# yuh.net
KiCad netlist of a schematic drawn in EAGLE
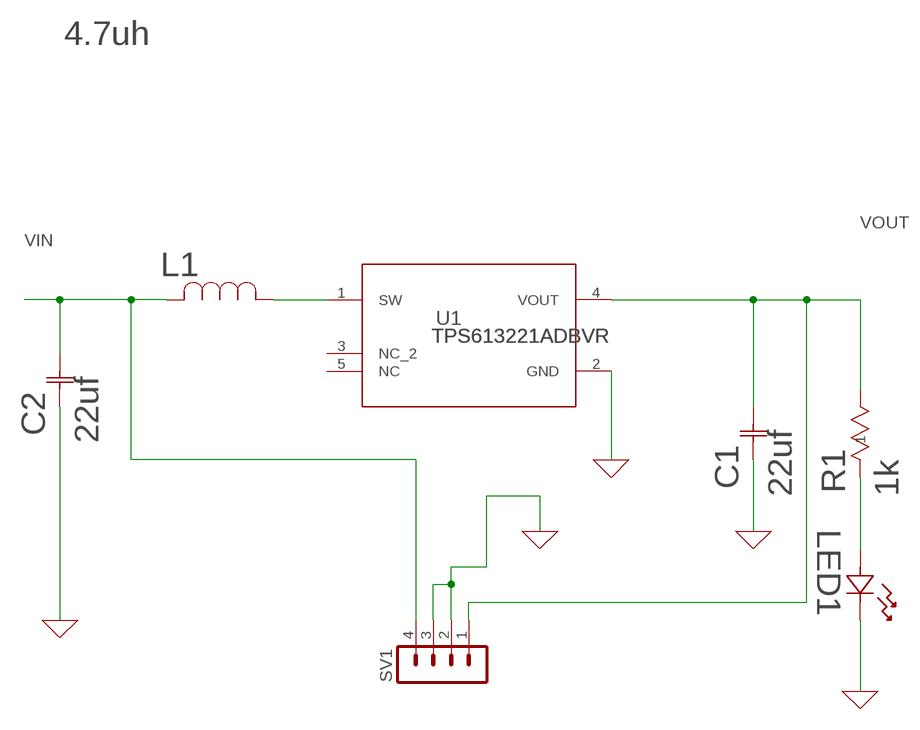
[diagram p0: schematic, sheet 1]

(export (version "E")
  (design (tool "Eeschema 10.0.6"))
  (components
    (comp (ref "C1")
      (value "22uf")
      (footprint "eagle-import:CAP_CL21_SAM")
      (fields
        (field (name "MANUFACTURER_PART_NUMBER") "CL21A226MQQNNNE")
        (field (name "COPYRIGHT") "Copyright (C) 2024 Ultra Librarian. All rights reserved.")
      )
      (libsource (lib "eagle-import") (part "CL21A226MQQNNNE"))
    )
    (comp (ref "C2")
      (value "22uf")
      (footprint "eagle-import:CAP_CL21_SAM")
      (fields
        (field (name "MANUFACTURER_PART_NUMBER") "CL21A226MQQNNNE")
        (field (name "COPYRIGHT") "Copyright (C) 2024 Ultra Librarian. All rights reserved.")
      )
      (libsource (lib "eagle-import") (part "CL21A226MQQNNNE"))
    )
    (comp (ref "L1")
      (value "4.7uh")
      (footprint "eagle-import:IND_LQM18PXXXXFRX_MUR")
      (fields
        (field (name "MANUFACTURER_PART_NUMBER") "LQM18PN4R7MFRL")
        (field (name "COPYRIGHT") "Copyright (C) 2024 Ultra Librarian. All rights reserved.")
      )
      (libsource (lib "eagle-import") (part "LQM18PN4R7MFRL"))
    )
    (comp (ref "LED1")
      (value "150080BS75000")
      (footprint "eagle-import:LED_BS75000_WRE")
      (fields (field (name "COPYRIGHT") "Copyright (C) 2024 Ultra Librarian. All rights reserved."))
      (libsource (lib "eagle-import") (part "150080BS75000"))
    )
    (comp (ref "R1")
      (value "1k")
      (footprint "eagle-import:RES_RC1206_YAG")
      (fields
        (field (name "MANUFACTURER_PART_NUMBER") "RC1206FR-071KL")
        (field (name "COPYRIGHT") "Copyright (C) 2024 Ultra Librarian. All rights reserved.")
      )
      (libsource (lib "eagle-import") (part "RC1206FR-071KL"))
    )
    (comp (ref "SV1")
      (value "MA04-1")
      (footprint "eagle-import:MA04-1")
      (libsource (lib "eagle-import") (part "MA04-1"))
    )
    (comp (ref "U1")
      (value "TPS613221ADBVR")
      (footprint "eagle-import:DBV0005A_N")
      (fields (field (name "COPYRIGHT") "Copyright (C) 2024 Ultra Librarian. All rights reserved."))
      (libsource (lib "eagle-import") (part "TPS613221ADBVR"))
    )
  )
  (nets
    (net (code "1") (name "/VIN") (class "Default")
      (node (ref "C2") (pin "2") (pinfunction "2_2") (pintype "passive"))
      (node (ref "L1") (pin "2") (pinfunction "2_2") (pintype "passive"))
      (node (ref "SV1") (pin "4") (pinfunction "4_4") (pintype "passive"))
    )
    (net (code "2") (name "/VOUT") (class "Default")
      (node (ref "C1") (pin "2") (pinfunction "2_2") (pintype "passive"))
      (node (ref "R1") (pin "2") (pinfunction "2_2") (pintype "passive"))
      (node (ref "SV1") (pin "1") (pinfunction "1_1") (pintype "passive"))
      (node (ref "U1") (pin "4") (pinfunction "VOUT_4") (pintype "power_in"))
    )
    (net (code "3") (name "GND") (class "Default")
      (node (ref "C1") (pin "1") (pinfunction "1_1") (pintype "passive"))
      (node (ref "C2") (pin "1") (pinfunction "1_1") (pintype "passive"))
      (node (ref "LED1") (pin "1") (pinfunction "1_1") (pintype "passive"))
      (node (ref "SV1") (pin "2") (pinfunction "2_2") (pintype "passive"))
      (node (ref "SV1") (pin "3") (pinfunction "3_3") (pintype "passive"))
      (node (ref "U1") (pin "2") (pinfunction "GND_2") (pintype "power_in"))
    )
    (net (code "4") (name "Net-(LED1-Pad2)") (class "Default")
      (node (ref "LED1") (pin "2") (pinfunction "2_2") (pintype "passive"))
      (node (ref "R1") (pin "1") (pinfunction "1_1") (pintype "passive"))
    )
    (net (code "5") (name "Net-(U1-SW)") (class "Default")
      (node (ref "L1") (pin "1") (pinfunction "1_1") (pintype "passive"))
      (node (ref "U1") (pin "1") (pinfunction "SW_1") (pintype "power_in"))
    )
    (net (code "6") (name "unconnected-(U1-NC-Pad5)") (class "Default")
      (node (ref "U1") (pin "5") (pinfunction "NC_5") (pintype "passive"))
    )
    (net (code "7") (name "unconnected-(U1-NC_2-Pad3)") (class "Default")
      (node (ref "U1") (pin "3") (pinfunction "NC_2_3") (pintype "passive"))
    )
  )
)
